# Opamp_Boost_Pedal.net
KiCad netlist of a schematic drawn in EAGLE
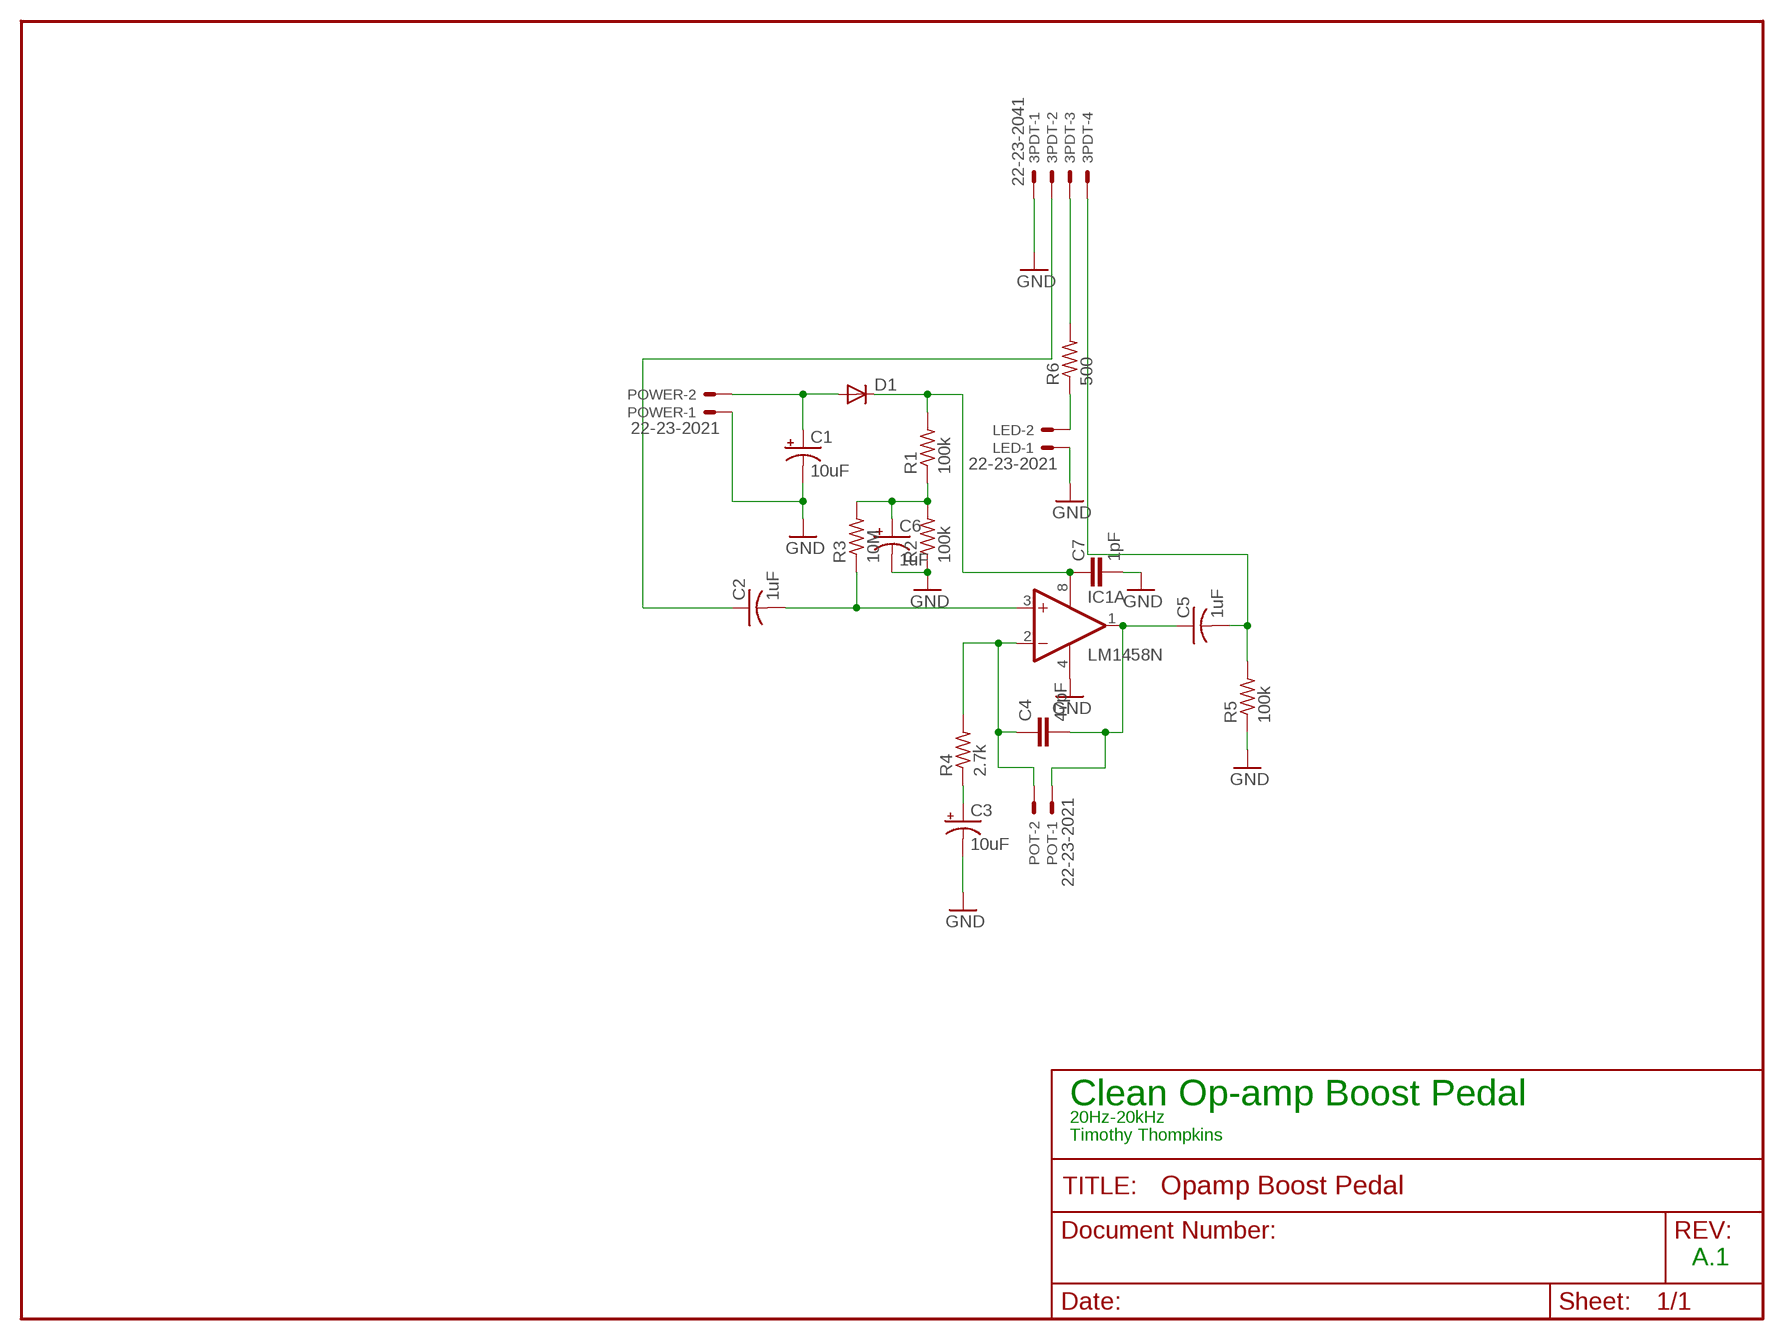
[diagram p0: schematic, sheet 1]

(export (version "E")
  (design (tool "Eeschema 10.0.6"))
  (components
    (comp (ref "3PDT")
      (value "22-23-2041")
      (footprint "eagle-import:22-23-2041")
      (libsource (lib "eagle-import") (part "22-23-2041"))
    )
    (comp (ref "C1")
      (value "10uF")
      (footprint "eagle-import:E5-5")
      (libsource (lib "eagle-import") (part "CPOL-USE5-5"))
    )
    (comp (ref "C2")
      (value "1uF")
      (footprint "eagle-import:C050-045X075")
      (libsource (lib "eagle-import") (part "C-US050-045X075"))
    )
    (comp (ref "C3")
      (value "10uF")
      (footprint "eagle-import:E5-5")
      (libsource (lib "eagle-import") (part "CPOL-USE5-5"))
    )
    (comp (ref "C4")
      (value "47pF")
      (footprint "eagle-import:C2.5-2")
      (libsource (lib "eagle-import") (part "C2.5/2"))
    )
    (comp (ref "C5")
      (value "1uF")
      (footprint "eagle-import:C050-045X075")
      (libsource (lib "eagle-import") (part "C-US050-045X075"))
    )
    (comp (ref "C6")
      (value "1uF")
      (footprint "eagle-import:E5-5")
      (libsource (lib "eagle-import") (part "CPOL-USE5-5"))
    )
    (comp (ref "C7")
      (value "1pF")
      (footprint "eagle-import:C2.5-2")
      (libsource (lib "eagle-import") (part "C2.5/2"))
    )
    (comp (ref "D1")
      (value "DIODE-D-2.5")
      (footprint "eagle-import:D-2.5")
      (libsource (lib "eagle-import") (part "DIODE-D-2.5"))
    )
    (comp (ref "IC1")
      (value "LM1458N")
      (footprint "eagle-import:DIL08")
      (libsource (lib "eagle-import") (part "1458NLM"))
    )
    (comp (ref "LED")
      (value "22-23-2021")
      (footprint "eagle-import:22-23-2021")
      (libsource (lib "eagle-import") (part "22-23-2021"))
    )
    (comp (ref "POT")
      (value "22-23-2021")
      (footprint "eagle-import:22-23-2021")
      (libsource (lib "eagle-import") (part "22-23-2021"))
    )
    (comp (ref "POWER")
      (value "22-23-2021")
      (footprint "eagle-import:22-23-2021")
      (libsource (lib "eagle-import") (part "22-23-2021"))
    )
    (comp (ref "R1")
      (value "100k")
      (footprint "eagle-import:0207_2V")
      (libsource (lib "eagle-import") (part "R-US_0207/2V"))
    )
    (comp (ref "R2")
      (value "100k")
      (footprint "eagle-import:0207_2V")
      (libsource (lib "eagle-import") (part "R-US_0207/2V"))
    )
    (comp (ref "R3")
      (value "10M")
      (footprint "eagle-import:0207_2V")
      (libsource (lib "eagle-import") (part "R-US_0207/2V"))
    )
    (comp (ref "R4")
      (value "2.7k")
      (footprint "eagle-import:0207_2V")
      (libsource (lib "eagle-import") (part "R-US_0207/2V"))
    )
    (comp (ref "R5")
      (value "100k")
      (footprint "eagle-import:0207_2V")
      (libsource (lib "eagle-import") (part "R-US_0207/2V"))
    )
    (comp (ref "R6")
      (value "500")
      (footprint "eagle-import:0207_2V")
      (libsource (lib "eagle-import") (part "R-US_0207/2V"))
    )
  )
  (nets
    (net (code "1") (name "GND") (class "Default")
      (node (ref "3PDT") (pin "1") (pinfunction "S_1") (pintype "passive"))
      (node (ref "C1") (pin "-") (pinfunction "-_-") (pintype "passive"))
      (node (ref "C3") (pin "-") (pinfunction "-_-") (pintype "passive"))
      (node (ref "C6") (pin "-") (pinfunction "-_-") (pintype "passive"))
      (node (ref "C7") (pin "2") (pinfunction "2_2") (pintype "passive"))
      (node (ref "IC1") (pin "4") (pinfunction "V-_4") (pintype "power_in"))
      (node (ref "LED") (pin "1") (pinfunction "S_1") (pintype "passive"))
      (node (ref "POWER") (pin "1") (pinfunction "S_1") (pintype "passive"))
      (node (ref "R2") (pin "1") (pinfunction "1_1") (pintype "passive"))
      (node (ref "R5") (pin "1") (pinfunction "1_1") (pintype "passive"))
    )
    (net (code "2") (name "Net-(3PDTB-S)") (class "Default")
      (node (ref "3PDT") (pin "2") (pinfunction "S_2") (pintype "passive"))
      (node (ref "C2") (pin "1") (pinfunction "1_1") (pintype "passive"))
    )
    (net (code "3") (name "Net-(3PDTC-S)") (class "Default")
      (node (ref "3PDT") (pin "3") (pinfunction "S_3") (pintype "passive"))
      (node (ref "R6") (pin "2") (pinfunction "2_2") (pintype "passive"))
    )
    (net (code "4") (name "Net-(3PDTD-S)") (class "Default")
      (node (ref "3PDT") (pin "4") (pinfunction "S_4") (pintype "passive"))
      (node (ref "C5") (pin "2") (pinfunction "2_2") (pintype "passive"))
      (node (ref "R5") (pin "2") (pinfunction "2_2") (pintype "passive"))
    )
    (net (code "5") (name "Net-(C3-Pad+)") (class "Default")
      (node (ref "C3") (pin "+") (pinfunction "+_+") (pintype "passive"))
      (node (ref "R4") (pin "1") (pinfunction "1_1") (pintype "passive"))
    )
    (net (code "6") (name "Net-(C6-Pad+)") (class "Default")
      (node (ref "C6") (pin "+") (pinfunction "+_+") (pintype "passive"))
      (node (ref "R1") (pin "1") (pinfunction "1_1") (pintype "passive"))
      (node (ref "R2") (pin "2") (pinfunction "2_2") (pintype "passive"))
      (node (ref "R3") (pin "2") (pinfunction "2_2") (pintype "passive"))
    )
    (net (code "7") (name "Net-(IC1A-+IN)") (class "Default")
      (node (ref "C2") (pin "2") (pinfunction "2_2") (pintype "passive"))
      (node (ref "IC1") (pin "3") (pinfunction "+IN_3") (pintype "input"))
      (node (ref "R3") (pin "1") (pinfunction "1_1") (pintype "passive"))
    )
    (net (code "8") (name "Net-(IC1A--IN)") (class "Default")
      (node (ref "C4") (pin "1") (pinfunction "1_1") (pintype "passive"))
      (node (ref "IC1") (pin "2") (pinfunction "-IN_2") (pintype "input"))
      (node (ref "POT") (pin "2") (pinfunction "S_2") (pintype "passive"))
      (node (ref "R4") (pin "2") (pinfunction "2_2") (pintype "passive"))
    )
    (net (code "9") (name "Net-(IC1A-OUT)") (class "Default")
      (node (ref "C4") (pin "2") (pinfunction "2_2") (pintype "passive"))
      (node (ref "C5") (pin "1") (pinfunction "1_1") (pintype "passive"))
      (node (ref "IC1") (pin "1") (pinfunction "OUT_1") (pintype "output"))
      (node (ref "POT") (pin "1") (pinfunction "S_1") (pintype "passive"))
    )
    (net (code "10") (name "Net-(IC1C-V+)") (class "Default")
      (node (ref "C7") (pin "1") (pinfunction "1_1") (pintype "passive"))
      (node (ref "D1") (pin "C") (pinfunction "C_C") (pintype "passive"))
      (node (ref "IC1") (pin "8") (pinfunction "V+_8") (pintype "power_in"))
      (node (ref "R1") (pin "2") (pinfunction "2_2") (pintype "passive"))
    )
    (net (code "11") (name "Net-(LEDB-S)") (class "Default")
      (node (ref "LED") (pin "2") (pinfunction "S_2") (pintype "passive"))
      (node (ref "R6") (pin "1") (pinfunction "1_1") (pintype "passive"))
    )
    (net (code "12") (name "Net-(POWERB-S)") (class "Default")
      (node (ref "C1") (pin "+") (pinfunction "+_+") (pintype "passive"))
      (node (ref "D1") (pin "A") (pinfunction "A_A") (pintype "passive"))
      (node (ref "POWER") (pin "2") (pinfunction "S_2") (pintype "passive"))
    )
  )
)
